# POWER.net
KiCad netlist of a schematic drawn in Altium Designer
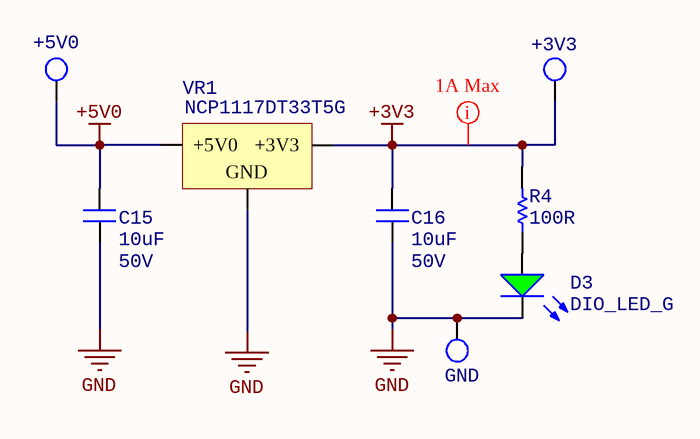
[diagram p0: POWER.SchDoc]

(export (version "E")
  (design (tool "Eeschema 10.0.6"))
  (components
    (comp (ref "+3V3")
      (value "TESTPOINT_LOOP")
      (footprint "TESTPOINT_LOOP")
      (description "Loop testpoint through-hole pad")
      (fields (field (name "MANUFACTURER") "Keystone Electronics"))
      (libsource (lib "UWRT_Schematic_Library_2020") (part "TESTPOINT_LOOP"))
    )
    (comp (ref "+5V0")
      (value "TESTPOINT_LOOP")
      (footprint "TESTPOINT_LOOP")
      (description "Loop testpoint through-hole pad")
      (fields (field (name "MANUFACTURER") "Keystone Electronics"))
      (libsource (lib "UWRT_Schematic_Library_2020") (part "TESTPOINT_LOOP"))
    )
    (comp (ref "C15")
      (value "10uF")
      (footprint "CAPC1206(3216)")
      (description "CAP CER 10UF 50V X5R 1206")
      (fields
        (field (name "MPN") "GRT31CR61H106KE01L")
        (field (name "MANUFACTURER") "Murata")
        (field (name "VOLTAGE RATING") "50V")
      )
      (libsource (lib "UWRT_Schematic_Library_2020") (part "CAP_10uF_50V_1206"))
    )
    (comp (ref "C16")
      (value "10uF")
      (footprint "CAPC1206(3216)")
      (description "CAP CER 10UF 50V X5R 1206")
      (fields
        (field (name "MPN") "GRT31CR61H106KE01L")
        (field (name "MANUFACTURER") "Murata")
        (field (name "VOLTAGE RATING") "50V")
      )
      (libsource (lib "UWRT_Schematic_Library_2020") (part "CAP_10uF_50V_1206"))
    )
    (comp (ref "D3")
      (value "DIO_LED_G")
      (footprint "LED_0805_LINE")
      (description "LED GREEN DIFFUSED 0805 SMD")
      (fields (field (name "MPN") "LG R971-KN-1") (field (name "MANUFACTURER") "OSRAM"))
      (libsource (lib "UWRT_Schematic_Library_2020") (part "DIO_LED_G"))
    )
    (comp (ref "GND")
      (value "TESTPOINT_LOOP")
      (footprint "TESTPOINT_LOOP")
      (description "Loop testpoint through-hole pad")
      (fields (field (name "MANUFACTURER") "Keystone Electronics"))
      (libsource (lib "UWRT_Schematic_Library_2020") (part "TESTPOINT_LOOP"))
    )
    (comp (ref "R4")
      (value "100R")
      (footprint "RESC0603(1608)_N")
      (description "RES SMD 100 OHM 1% 1/10W 0603")
      (fields (field (name "MANUFACTURER") "Yageo") (field (name "MPN") "RC0603FR-07100RL"))
      (libsource (lib "UWRT_Schematic_Library_2020") (part "RES_100R_0603"))
    )
    (comp (ref "VR1")
      (value "5V0_3V3_LDO")
      (footprint "VOLTAGE_REGULATOR")
      (description "IC REG LINEAR 3.3V 1A DPAK")
      (fields (field (name "MPN") "NCP1117DT33T5G") (field (name "MANUFACTURER") "ON Semiconductor"))
      (libsource (lib "UWRT_Schematic_Library_2020") (part "5V0_3V3_LDO"))
    )
  )
  (nets
    (net (code "1") (name "+3V3") (class "Default")
      (node (ref "+3V3") (pin "1") (pintype "passive"))
      (node (ref "C16") (pin "2") (pinfunction "2_2") (pintype "passive"))
      (node (ref "R4") (pin "2") (pinfunction "2_2") (pintype "passive"))
      (node (ref "VR1") (pin "2") (pinfunction "+3V3_2") (pintype "passive"))
    )
    (net (code "2") (name "+5V0") (class "Default")
      (node (ref "+5V0") (pin "1") (pintype "passive"))
      (node (ref "C15") (pin "2") (pinfunction "2_2") (pintype "passive"))
      (node (ref "VR1") (pin "3") (pinfunction "+5V0_3") (pintype "passive"))
    )
    (net (code "3") (name "GND") (class "Default")
      (node (ref "C15") (pin "1") (pinfunction "1_1") (pintype "passive"))
      (node (ref "C16") (pin "1") (pinfunction "1_1") (pintype "passive"))
      (node (ref "D3") (pin "2") (pinfunction "K_2") (pintype "passive"))
      (node (ref "GND") (pin "1") (pintype "passive"))
      (node (ref "VR1") (pin "1") (pinfunction "GND_1") (pintype "passive"))
    )
    (net (code "4") (name "Net-(D3-A)") (class "Default")
      (node (ref "D3") (pin "1") (pinfunction "A_1") (pintype "passive"))
      (node (ref "R4") (pin "1") (pinfunction "1_1") (pintype "passive"))
    )
  )
)
